# Sheet2.net
KiCad netlist of a schematic drawn in Altium Designer
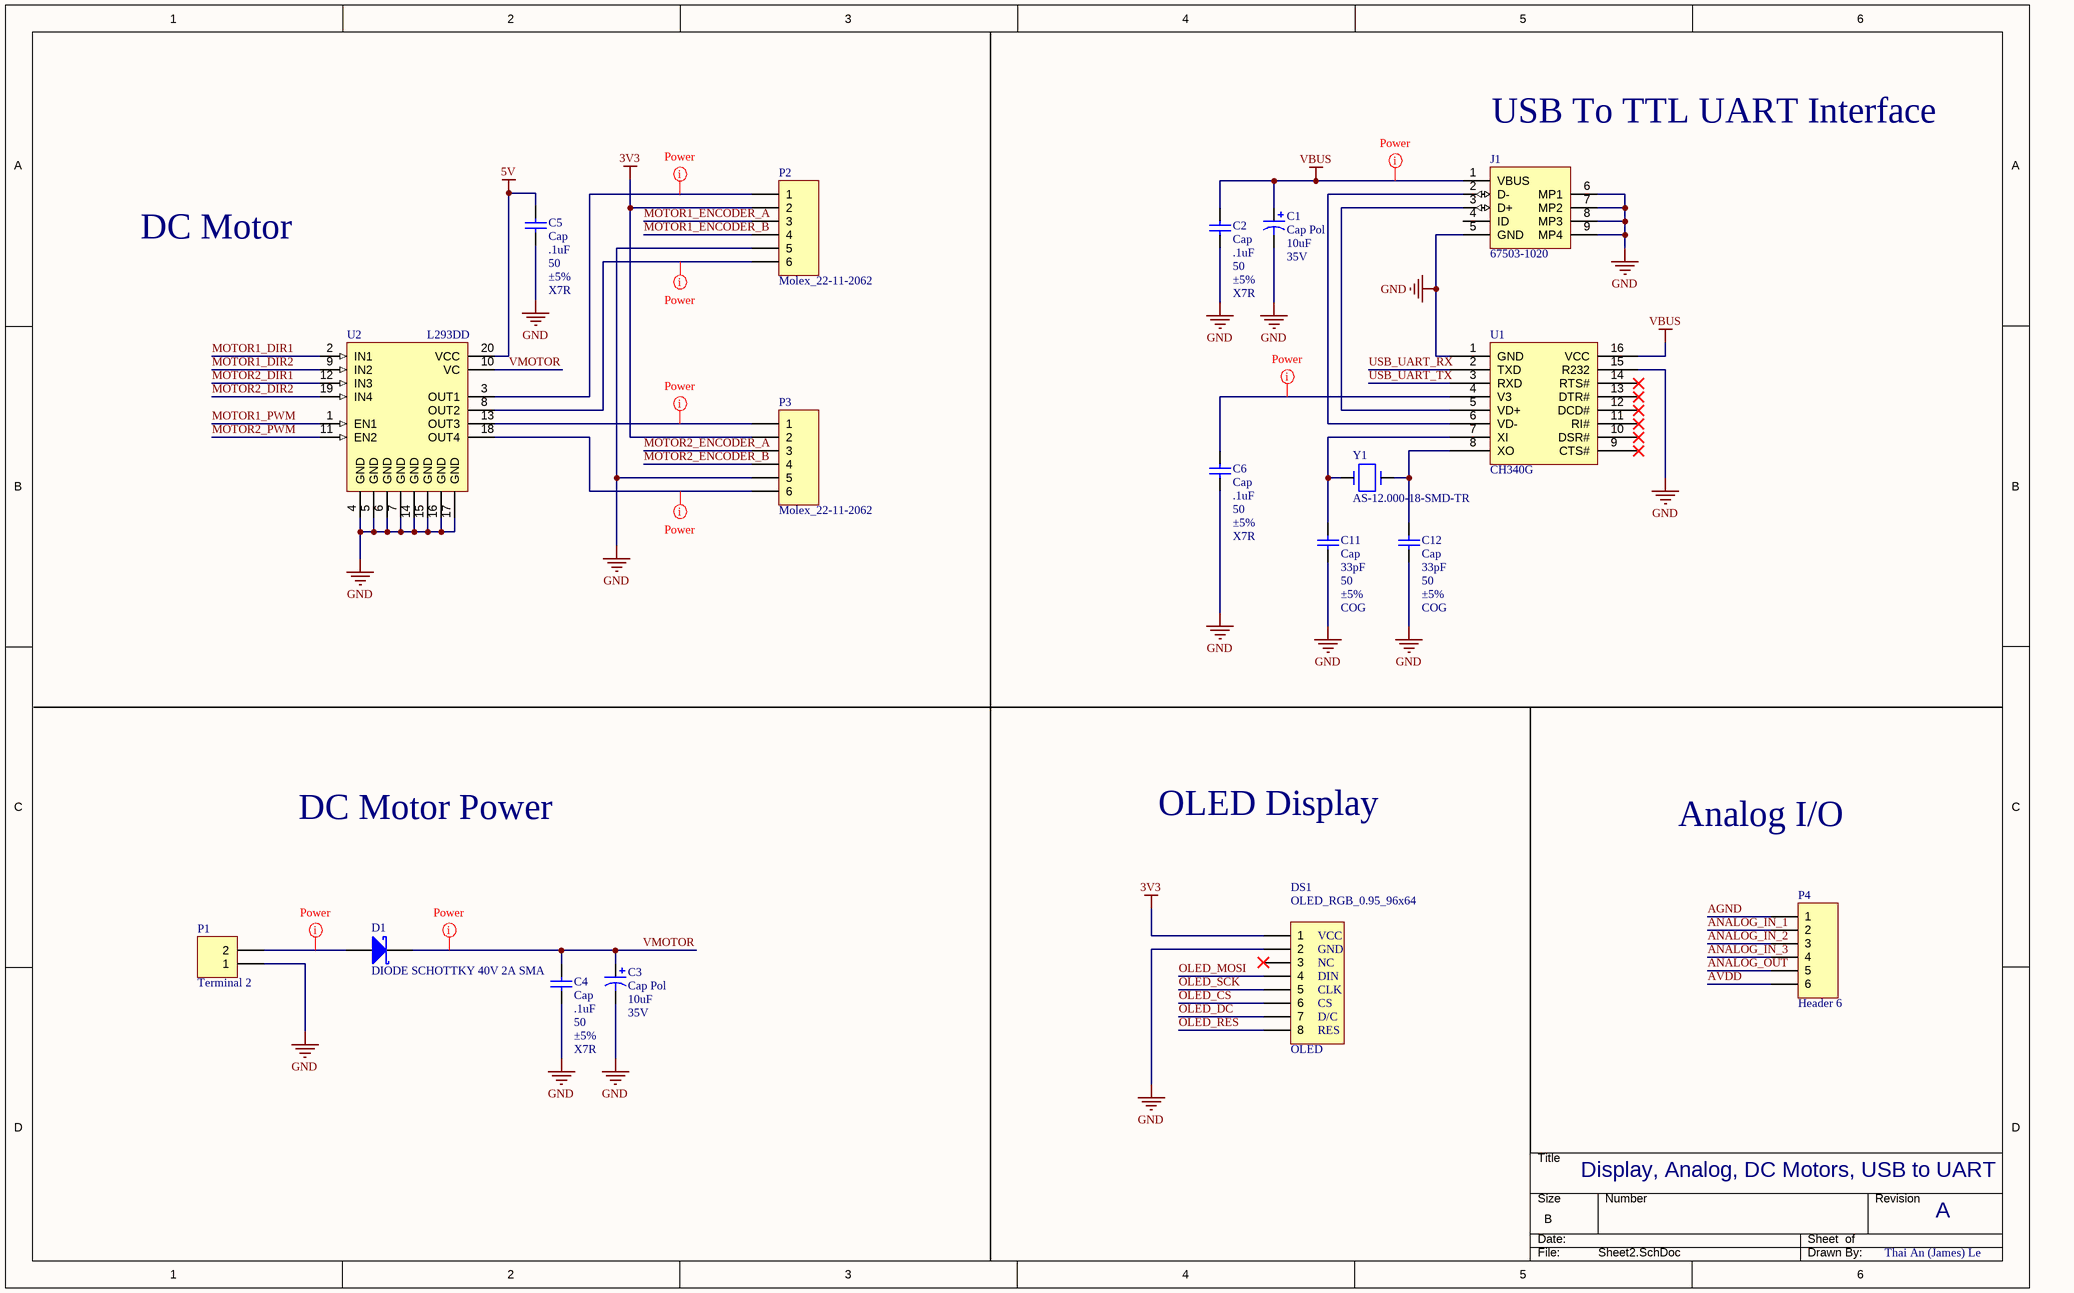
[diagram p0: Sheet2.SchDoc]

(export (version "E")
  (design (tool "Eeschema 10.0.6"))
  (components
    (comp (ref "C1")
      (value "Cap Pol")
      (footprint "CAPACITOR_5MM")
      (description "CAP 85C 10uF ±20% 35V WX Series Aluminum Electrolytic")
      (fields
        (field (name "ALTIUM_VALUE") "10uF")
        (field (name "VOLTAGE") "35V")
        (field (name "MPN") "UWX1V100MCL1GB")
      )
      (libsource (lib "esd_library") (part "Cap Polar-10uF-35V"))
    )
    (comp (ref "C2")
      (value "Cap")
      (footprint "CAPC2012X09M")
      (description "CAP CER .1uF 50v X7R 0805")
      (fields
        (field (name "ALTIUM_VALUE") ".1uF")
        (field (name "WV") "50")
        (field (name "TOLERANCE") "±5%")
        (field (name "TYPE") "X7R")
        (field (name "MPN") "C0805C104J5RACTU")
      )
      (libsource (lib "esd_library") (part "CAP-X7R-.1uF-50V-±5%"))
    )
    (comp (ref "C3")
      (value "Cap Pol")
      (footprint "CAPACITOR_5MM")
      (description "CAP 85C 10uF ±20% 35V WX Series Aluminum Electrolytic")
      (fields
        (field (name "ALTIUM_VALUE") "10uF")
        (field (name "VOLTAGE") "35V")
        (field (name "MPN") "UWX1V100MCL1GB")
      )
      (libsource (lib "esd_library") (part "Cap Polar-10uF-35V"))
    )
    (comp (ref "C4")
      (value "Cap")
      (footprint "CAPC2012X09M")
      (description "CAP CER .1uF 50v X7R 0805")
      (fields
        (field (name "ALTIUM_VALUE") ".1uF")
        (field (name "WV") "50")
        (field (name "TOLERANCE") "±5%")
        (field (name "TYPE") "X7R")
        (field (name "MPN") "C0805C104J5RACTU")
      )
      (libsource (lib "esd_library") (part "CAP-X7R-.1uF-50V-±5%"))
    )
    (comp (ref "C5")
      (value "Cap")
      (footprint "CAPC2012X09M")
      (description "CAP CER .1uF 50v X7R 0805")
      (fields
        (field (name "ALTIUM_VALUE") ".1uF")
        (field (name "WV") "50")
        (field (name "TOLERANCE") "±5%")
        (field (name "TYPE") "X7R")
        (field (name "MPN") "C0805C104J5RACTU")
      )
      (libsource (lib "esd_library") (part "CAP-X7R-.1uF-50V-±5%"))
    )
    (comp (ref "C6")
      (value "Cap")
      (footprint "CAPC2012X09M")
      (description "CAP CER .1uF 50v X7R 0805")
      (fields
        (field (name "ALTIUM_VALUE") ".1uF")
        (field (name "WV") "50")
        (field (name "TOLERANCE") "±5%")
        (field (name "TYPE") "X7R")
        (field (name "MPN") "C0805C104J5RACTU")
      )
      (libsource (lib "esd_library") (part "CAP-X7R-.1uF-50V-±5%"))
    )
    (comp (ref "C11")
      (value "Cap")
      (footprint "CAPC2012X09M")
      (description "CAP CER 33pF 50v COG 0805")
      (fields
        (field (name "ALTIUM_VALUE") "33pF")
        (field (name "WV") "50")
        (field (name "TOLERANCE") "±5%")
        (field (name "TYPE") "COG")
        (field (name "MPN") "C0805C330J5GACTU")
      )
      (libsource (lib "esd_library") (part "CAP-COG-33pF-50V-±5%"))
    )
    (comp (ref "C12")
      (value "Cap")
      (footprint "CAPC2012X09M")
      (description "CAP CER 33pF 50v COG 0805")
      (fields
        (field (name "ALTIUM_VALUE") "33pF")
        (field (name "WV") "50")
        (field (name "TOLERANCE") "±5%")
        (field (name "TYPE") "COG")
        (field (name "MPN") "C0805C330J5GACTU")
      )
      (libsource (lib "esd_library") (part "CAP-COG-33pF-50V-±5%"))
    )
    (comp (ref "D1")
      (value "DIODE SCHOTTKY 40V 2A SMA")
      (footprint "DIOM4326X23M")
      (description "Schottky Rectifier")
      (fields (field (name "MPN") "B240A-13-F"))
      (libsource (lib "esd_library") (part "DIODE SCHOTTKY 40V 2A SMA"))
    )
    (comp (ref "DS1")
      (value "OLED")
      (footprint "OLED_RGB_0.95_96x64_Waveshare")
      (description "Waveshare 0.95 inch OLED Module")
      (fields (field (name "MPN") "PPPC081LFBN-RC"))
      (libsource (lib "esd_library") (part "OLED_RGB_0.95_96x64_Waveshare"))
    )
    (comp (ref "J1")
      (value "67503-1020")
      (footprint "MOLX-67503-1020_V")
      (description "USB, MINI, SMD, RA KME04-USBMU03A01")
      (fields (field (name "MANUFACTURER") "Molex"))
      (libsource (lib "esd_library") (part "MOLX-67503-1020"))
    )
    (comp (ref "P1")
      (value "Terminal 2")
      (footprint "TYCO_282841_2")
      (description "Terminal, 2-Pin")
      (fields (field (name "MPN") "282841-2") (field (name "PUBLISHER") "Altium Limited"))
      (libsource (lib "esd_library") (part "Terminal 2"))
    )
    (comp (ref "P2")
      (value "Molex_22-11-2062")
      (footprint "MOLEX_22-11-2062")
      (description "CONN HEADER 6POS .100 VERT GOLD")
      (fields (field (name "MPN") "0022112062"))
      (libsource (lib "esd_library") (part "Molex_22-11-2062"))
    )
    (comp (ref "P3")
      (value "Molex_22-11-2062")
      (footprint "MOLEX_22-11-2062")
      (description "CONN HEADER 6POS .100 VERT GOLD")
      (fields (field (name "MPN") "0022112062"))
      (libsource (lib "esd_library") (part "Molex_22-11-2062"))
    )
    (comp (ref "P4")
      (value "Header 6")
      (footprint "HDR1X6")
      (description "Header, 6-Pin Male")
      (fields (field (name "MPN") "PEC06SFAN"))
      (libsource (lib "esd_library") (part "Header 6"))
    )
    (comp (ref "U1")
      (value "CH340G")
      (footprint "NSO16_L")
      (description "USB to serial chip")
      (libsource (lib "esd_library") (part "CH340G"))
    )
    (comp (ref "U2")
      (value "L293DD")
      (footprint "SO20_N")
      (description "IC MOTOR DRIVER PAR 20-SOIC")
      (fields (field (name "MPN") "L293DD013TR") (field (name "PUBLISHER") "Altium Limited"))
      (libsource (lib "esd_library") (part "L293DD"))
    )
    (comp (ref "Y1")
      (value "AS-12.000-18-SMD-TR")
      (footprint "HCS-49/U")
      (description "CRYSTAL 12.0000MHZ 18PF SMD")
      (libsource (lib "esd_library") (part "AS-12.000-18-SMD-TR"))
    )
  )
  (nets
    (net (code "1") (name "/AGND") (class "Default")
      (node (ref "P4") (pin "1") (pinfunction "1_1") (pintype "passive"))
    )
    (net (code "2") (name "/ANALOG_IN_1") (class "Default")
      (node (ref "P4") (pin "2") (pinfunction "2_2") (pintype "passive"))
    )
    (net (code "3") (name "/ANALOG_IN_2") (class "Default")
      (node (ref "P4") (pin "3") (pinfunction "3_3") (pintype "passive"))
    )
    (net (code "4") (name "/ANALOG_IN_3") (class "Default")
      (node (ref "P4") (pin "4") (pinfunction "4_4") (pintype "passive"))
    )
    (net (code "5") (name "/ANALOG_OUT") (class "Default")
      (node (ref "P4") (pin "5") (pinfunction "5_5") (pintype "passive"))
    )
    (net (code "6") (name "/AVDD") (class "Default")
      (node (ref "P4") (pin "6") (pinfunction "6_6") (pintype "passive"))
    )
    (net (code "7") (name "/MOTOR1_DIR1") (class "Default")
      (node (ref "U2") (pin "2") (pinfunction "IN1_2") (pintype "input"))
    )
    (net (code "8") (name "/MOTOR1_DIR2") (class "Default")
      (node (ref "U2") (pin "9") (pinfunction "IN2_9") (pintype "input"))
    )
    (net (code "9") (name "/MOTOR1_ENCODER_A") (class "Default")
      (node (ref "P2") (pin "3") (pinfunction "3_3") (pintype "passive"))
    )
    (net (code "10") (name "/MOTOR1_ENCODER_B") (class "Default")
      (node (ref "P2") (pin "4") (pinfunction "4_4") (pintype "passive"))
    )
    (net (code "11") (name "/MOTOR1_PWM") (class "Default")
      (node (ref "U2") (pin "1") (pinfunction "EN1_1") (pintype "input"))
    )
    (net (code "12") (name "/MOTOR2_DIR1") (class "Default")
      (node (ref "U2") (pin "12") (pinfunction "IN3_12") (pintype "input"))
    )
    (net (code "13") (name "/MOTOR2_DIR2") (class "Default")
      (node (ref "U2") (pin "19") (pinfunction "IN4_19") (pintype "input"))
    )
    (net (code "14") (name "/MOTOR2_ENCODER_A") (class "Default")
      (node (ref "P3") (pin "3") (pinfunction "3_3") (pintype "passive"))
    )
    (net (code "15") (name "/MOTOR2_ENCODER_B") (class "Default")
      (node (ref "P3") (pin "4") (pinfunction "4_4") (pintype "passive"))
    )
    (net (code "16") (name "/MOTOR2_PWM") (class "Default")
      (node (ref "U2") (pin "11") (pinfunction "EN2_11") (pintype "input"))
    )
    (net (code "17") (name "/OLED_CS") (class "Default")
      (node (ref "DS1") (pin "6") (pinfunction "6_6") (pintype "passive"))
    )
    (net (code "18") (name "/OLED_DC") (class "Default")
      (node (ref "DS1") (pin "7") (pinfunction "7_7") (pintype "passive"))
    )
    (net (code "19") (name "/OLED_MOSI") (class "Default")
      (node (ref "DS1") (pin "4") (pinfunction "4_4") (pintype "passive"))
    )
    (net (code "20") (name "/OLED_RES") (class "Default")
      (node (ref "DS1") (pin "8") (pinfunction "8_8") (pintype "passive"))
    )
    (net (code "21") (name "/OLED_SCK") (class "Default")
      (node (ref "DS1") (pin "5") (pinfunction "5_5") (pintype "passive"))
    )
    (net (code "22") (name "/USB_UART_RX") (class "Default")
      (node (ref "U1") (pin "2") (pinfunction "TXD_2") (pintype "passive"))
    )
    (net (code "23") (name "/USB_UART_TX") (class "Default")
      (node (ref "U1") (pin "3") (pinfunction "RXD_3") (pintype "passive"))
    )
    (net (code "24") (name "/VMOTOR") (class "Default")
      (node (ref "C3") (pin "1") (pinfunction "1_1") (pintype "passive"))
      (node (ref "C4") (pin "2") (pinfunction "2_2") (pintype "passive"))
      (node (ref "D1") (pin "1") (pinfunction "K_1") (pintype "passive"))
      (node (ref "U2") (pin "10") (pinfunction "VC_10") (pintype "power_in"))
    )
    (net (code "25") (name "3V3") (class "Default")
      (node (ref "DS1") (pin "1") (pinfunction "1_1") (pintype "passive"))
      (node (ref "P2") (pin "2") (pinfunction "2_2") (pintype "passive"))
      (node (ref "P3") (pin "2") (pinfunction "2_2") (pintype "passive"))
    )
    (net (code "26") (name "5V") (class "Default")
      (node (ref "C5") (pin "2") (pinfunction "2_2") (pintype "passive"))
      (node (ref "U2") (pin "20") (pinfunction "VCC_20") (pintype "power_in"))
    )
    (net (code "27") (name "GND") (class "Default")
      (node (ref "C1") (pin "2") (pinfunction "2_2") (pintype "passive"))
      (node (ref "C11") (pin "1") (pinfunction "1_1") (pintype "passive"))
      (node (ref "C12") (pin "1") (pinfunction "1_1") (pintype "passive"))
      (node (ref "C2") (pin "1") (pinfunction "1_1") (pintype "passive"))
      (node (ref "C3") (pin "2") (pinfunction "2_2") (pintype "passive"))
      (node (ref "C4") (pin "1") (pinfunction "1_1") (pintype "passive"))
      (node (ref "C5") (pin "1") (pinfunction "1_1") (pintype "passive"))
      (node (ref "C6") (pin "1") (pinfunction "1_1") (pintype "passive"))
      (node (ref "DS1") (pin "2") (pinfunction "2_2") (pintype "passive"))
      (node (ref "J1") (pin "5") (pinfunction "GND_5") (pintype "power_in"))
      (node (ref "J1") (pin "6") (pinfunction "MP1_6") (pintype "passive"))
      (node (ref "J1") (pin "7") (pinfunction "MP2_7") (pintype "passive"))
      (node (ref "J1") (pin "8") (pinfunction "MP3_8") (pintype "passive"))
      (node (ref "J1") (pin "9") (pinfunction "MP4_9") (pintype "passive"))
      (node (ref "P1") (pin "1") (pinfunction "1_1") (pintype "passive"))
      (node (ref "P2") (pin "5") (pinfunction "5_5") (pintype "passive"))
      (node (ref "P3") (pin "5") (pinfunction "5_5") (pintype "passive"))
      (node (ref "U1") (pin "1") (pinfunction "GND_1") (pintype "passive"))
      (node (ref "U1") (pin "15") (pinfunction "R232_15") (pintype "passive"))
      (node (ref "U2") (pin "14") (pinfunction "GND_14") (pintype "power_in"))
      (node (ref "U2") (pin "15") (pinfunction "GND_15") (pintype "power_in"))
      (node (ref "U2") (pin "16") (pinfunction "GND_16") (pintype "power_in"))
      (node (ref "U2") (pin "17") (pinfunction "GND_17") (pintype "power_in"))
      (node (ref "U2") (pin "4") (pinfunction "GND_4") (pintype "power_in"))
      (node (ref "U2") (pin "5") (pinfunction "GND_5") (pintype "power_in"))
      (node (ref "U2") (pin "6") (pinfunction "GND_6") (pintype "power_in"))
      (node (ref "U2") (pin "7") (pinfunction "GND_7") (pintype "power_in"))
    )
    (net (code "28") (name "Net-(D1-A)") (class "Default")
      (node (ref "D1") (pin "2") (pinfunction "A_2") (pintype "passive"))
      (node (ref "P1") (pin "2") (pinfunction "2_2") (pintype "passive"))
    )
    (net (code "29") (name "Net-(J1-D+)") (class "Default")
      (node (ref "J1") (pin "3") (pinfunction "D+_3") (pintype "bidirectional"))
      (node (ref "U1") (pin "5") (pinfunction "VD+_5") (pintype "passive"))
    )
    (net (code "30") (name "Net-(J1-D-)") (class "Default")
      (node (ref "J1") (pin "2") (pinfunction "D-_2") (pintype "bidirectional"))
      (node (ref "U1") (pin "6") (pinfunction "VD-_6") (pintype "passive"))
    )
    (net (code "31") (name "Net-(U1-V3)") (class "Default")
      (node (ref "C6") (pin "2") (pinfunction "2_2") (pintype "passive"))
      (node (ref "U1") (pin "4") (pinfunction "V3_4") (pintype "passive"))
    )
    (net (code "32") (name "Net-(U1-XI)") (class "Default")
      (node (ref "C11") (pin "2") (pinfunction "2_2") (pintype "passive"))
      (node (ref "U1") (pin "7") (pinfunction "XI_7") (pintype "passive"))
      (node (ref "Y1") (pin "1") (pinfunction "1_1") (pintype "passive"))
    )
    (net (code "33") (name "Net-(U1-XO)") (class "Default")
      (node (ref "C12") (pin "2") (pinfunction "2_2") (pintype "passive"))
      (node (ref "U1") (pin "8") (pinfunction "XO_8") (pintype "passive"))
      (node (ref "Y1") (pin "2") (pinfunction "2_2") (pintype "passive"))
    )
    (net (code "34") (name "Net-(U2-OUT1)") (class "Default")
      (node (ref "P2") (pin "1") (pinfunction "1_1") (pintype "passive"))
      (node (ref "U2") (pin "3") (pinfunction "OUT1_3") (pintype "tri_state"))
    )
    (net (code "35") (name "Net-(U2-OUT2)") (class "Default")
      (node (ref "P2") (pin "6") (pinfunction "6_6") (pintype "passive"))
      (node (ref "U2") (pin "8") (pinfunction "OUT2_8") (pintype "tri_state"))
    )
    (net (code "36") (name "Net-(U2-OUT3)") (class "Default")
      (node (ref "P3") (pin "1") (pinfunction "1_1") (pintype "passive"))
      (node (ref "U2") (pin "13") (pinfunction "OUT3_13") (pintype "tri_state"))
    )
    (net (code "37") (name "Net-(U2-OUT4)") (class "Default")
      (node (ref "P3") (pin "6") (pinfunction "6_6") (pintype "passive"))
      (node (ref "U2") (pin "18") (pinfunction "OUT4_18") (pintype "tri_state"))
    )
    (net (code "38") (name "VBUS") (class "Default")
      (node (ref "C1") (pin "1") (pinfunction "1_1") (pintype "passive"))
      (node (ref "C2") (pin "2") (pinfunction "2_2") (pintype "passive"))
      (node (ref "J1") (pin "1") (pinfunction "VBUS_1") (pintype "power_in"))
      (node (ref "U1") (pin "16") (pinfunction "VCC_16") (pintype "passive"))
    )
    (net (code "39") (name "unconnected-(DS1-Pad3)") (class "Default")
      (node (ref "DS1") (pin "3") (pinfunction "3_3") (pintype "passive+no_connect"))
    )
    (net (code "40") (name "unconnected-(J1-ID-Pad4)") (class "Default")
      (node (ref "J1") (pin "4") (pinfunction "ID_4") (pintype "passive"))
    )
    (net (code "41") (name "unconnected-(U1-CTS#-Pad9)") (class "Default")
      (node (ref "U1") (pin "9") (pinfunction "CTS#_9") (pintype "passive+no_connect"))
    )
    (net (code "42") (name "unconnected-(U1-DCD#-Pad12)") (class "Default")
      (node (ref "U1") (pin "12") (pinfunction "DCD#_12") (pintype "passive+no_connect"))
    )
    (net (code "43") (name "unconnected-(U1-DSR#-Pad10)") (class "Default")
      (node (ref "U1") (pin "10") (pinfunction "DSR#_10") (pintype "passive+no_connect"))
    )
    (net (code "44") (name "unconnected-(U1-DTR#-Pad13)") (class "Default")
      (node (ref "U1") (pin "13") (pinfunction "DTR#_13") (pintype "passive+no_connect"))
    )
    (net (code "45") (name "unconnected-(U1-RI#-Pad11)") (class "Default")
      (node (ref "U1") (pin "11") (pinfunction "RI#_11") (pintype "passive+no_connect"))
    )
    (net (code "46") (name "unconnected-(U1-RTS#-Pad14)") (class "Default")
      (node (ref "U1") (pin "14") (pinfunction "RTS#_14") (pintype "passive+no_connect"))
    )
  )
)
